# Microcontroller.net
KiCad netlist of a schematic drawn in Altium Designer
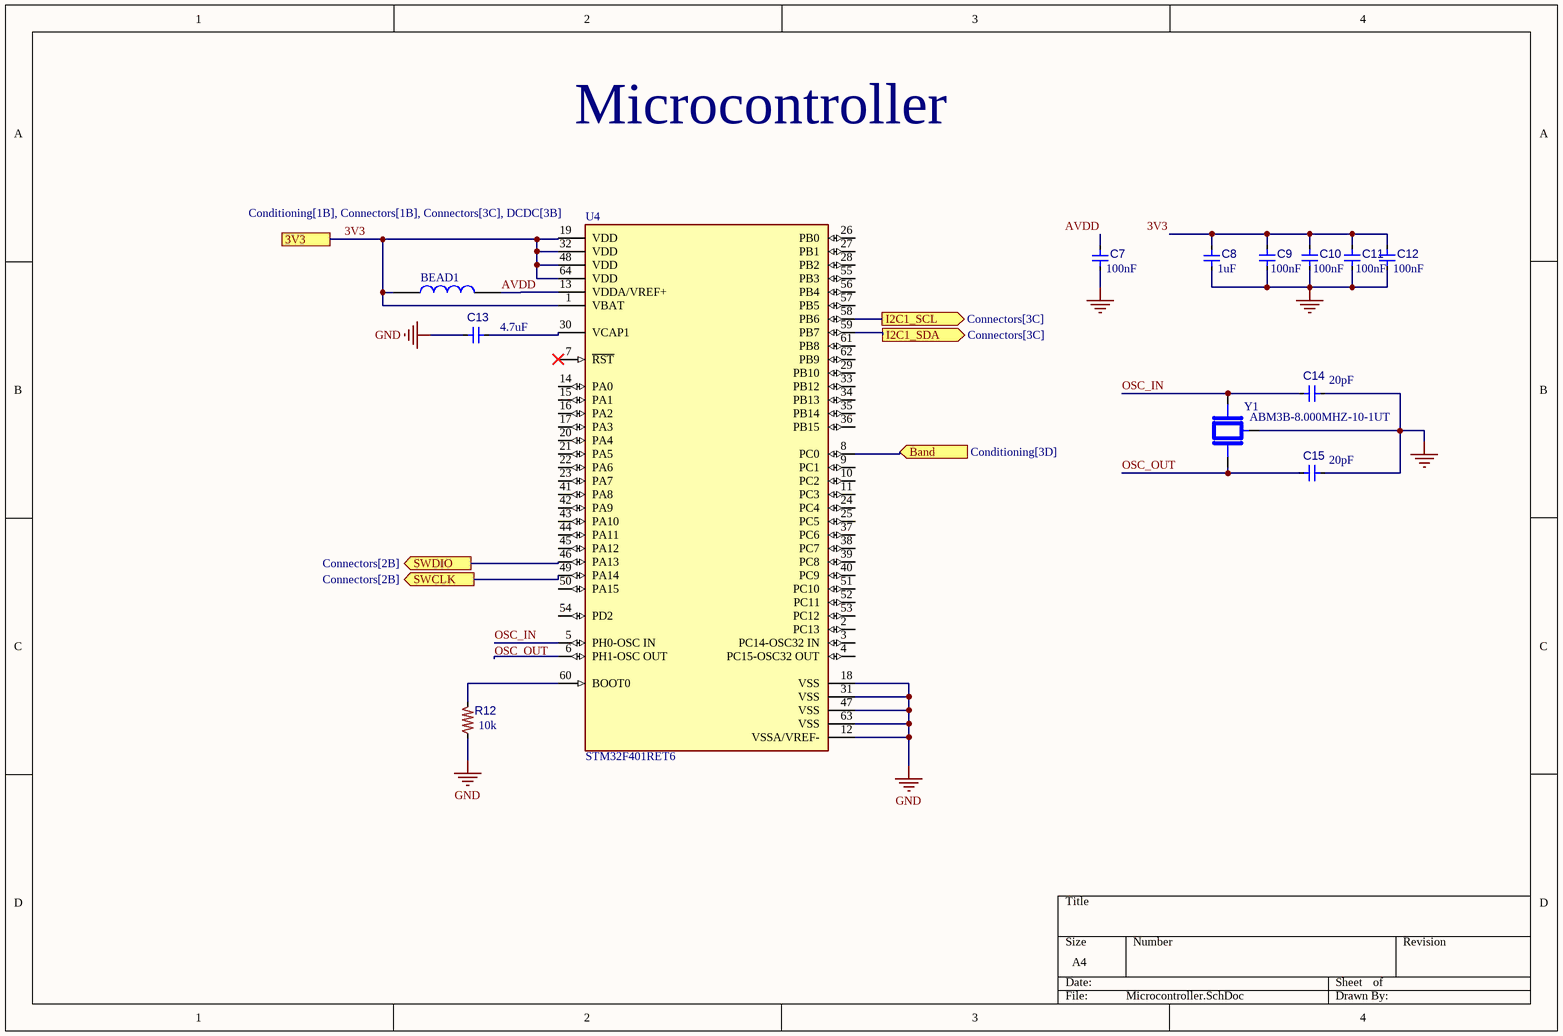
[diagram p0: Microcontroller.SchDoc]

(export (version "E")
  (design (tool "Eeschema 10.0.6"))
  (components
    (comp (ref "BEAD1")
      (value "C710390")
      (footprint "BEADC1608X95N")
      (description "MURATA Ferrite Beads 120 OHM - BLM18SG121TZ1D")
      (fields
        (field (name "MOUSER PART NUMBER") "791-WLBD1608K1U601TB")
        (field (name "MANUFACTURER_PART_NUMBER") "WLBD1608K1U601TB")
      )
      (libsource (lib "Muner") (part "WLBD1608K1U601TB"))
    )
    (comp (ref "C7")
      (value "C105907")
      (footprint "New footprint 1")
      (description "100V 100nF X7R ±10% 0603  Multilayer Ceramic Capacitors MLCC - SMD/SMT ROHS")
      (libsource (lib "Muner") (part "CAP-NP-2"))
    )
    (comp (ref "C8")
      (value "C309479")
      (footprint "New footprint 1")
      (description "6.3V 1uF X7R ±10% 0603  Multilayer Ceramic Capacitors MLCC - SMD/SMT ROHS")
      (libsource (lib "Muner") (part "CAP-NP-2"))
    )
    (comp (ref "C9")
      (value "C105907")
      (footprint "New footprint 1")
      (description "100V 100nF X7R ±10% 0603  Multilayer Ceramic Capacitors MLCC - SMD/SMT ROHS")
      (libsource (lib "Muner") (part "CAP-NP-2"))
    )
    (comp (ref "C10")
      (value "C105907")
      (footprint "New footprint 1")
      (description "100V 100nF X7R ±10% 0603  Multilayer Ceramic Capacitors MLCC - SMD/SMT ROHS")
      (libsource (lib "Muner") (part "CAP-NP-2"))
    )
    (comp (ref "C11")
      (value "C105907")
      (footprint "New footprint 1")
      (description "100V 100nF X7R ±10% 0603  Multilayer Ceramic Capacitors MLCC - SMD/SMT ROHS")
      (libsource (lib "Muner") (part "CAP-NP-2"))
    )
    (comp (ref "C12")
      (value "C105907")
      (footprint "New footprint 1")
      (description "100V 100nF X7R ±10% 0603  Multilayer Ceramic Capacitors MLCC - SMD/SMT ROHS")
      (libsource (lib "Muner") (part "CAP-NP-2"))
    )
    (comp (ref "C13")
      (value "C77045")
      (footprint "New footprint 1")
      (description "116V 4.7uF X5R ±10% 0603 Multilayer Ceramic Capacitors MLCC - SMD/SMT ROHS")
      (libsource (lib "Muner") (part "CAP-NP-2"))
    )
    (comp (ref "C14")
      (value "C63680")
      (footprint "New footprint 1")
      (description "200V 20pF C0G ±5% 0603 Multilayer Ceramic Capacitors MLCC - SMD/SMT ROHS")
      (libsource (lib "Muner") (part "CAP-NP-2"))
    )
    (comp (ref "C15")
      (value "C63680")
      (footprint "New footprint 1")
      (description "200V 20pF C0G ±5% 0603 Multilayer Ceramic Capacitors MLCC - SMD/SMT ROHS")
      (libsource (lib "Muner") (part "CAP-NP-2"))
    )
    (comp (ref "R12")
      (value "C103210")
      (footprint "0603 resistor-Footprint-1")
      (description "100mW Thick Film Resistors ±100ppm/℃ ±5% 10kΩ 0603 Chip Resistor - Surface Mount ROHS")
      (libsource (lib "Muner") (part "RES-2"))
    )
    (comp (ref "U4")
      (value "STM32F401RET6")
      (footprint "FP-LQFP64-5W-MFG")
      (description "512KB 1.7V~3.6V ARM Cortex-M4 84MHz 50 LQFP-64(10x10)  Microcontroller Units (MCUs/MPUs/SOCs) ROHS")
      (fields
        (field (name "OCTOPART") "https://octopart.com/stm32f401ret6-stmicroelectronics-34185993")
        (field (name "MANUFACTURER") "STMicroelectronics")
      )
      (libsource (lib "Altium Content Vault") (part "7f49e7cdc56bbeda8d86db7d775c506"))
    )
    (comp (ref "Y1")
      (value "ABM3B-8.000MHZ-10-1UT")
      (footprint "XTAL_ABM3B-8.000MHZ-10-1UT")
      (description "Crystal 8MHz Â±10ppm (Tol) Â±10ppm (Stability) 10pF FUND 200Ohm 4-Pin CSMD T/R")
      (fields (field (name "MF") "Abracon Corporation"))
      (libsource (lib "Muner") (part "CMP-003-00030-3"))
    )
  )
  (nets
    (net (code "1") (name "/3V3") (class "Default")
      (node (ref "BEAD1") (pin "1") (pinfunction "1_1") (pintype "passive"))
      (node (ref "C10") (pin "2") (pinfunction "2_2") (pintype "passive"))
      (node (ref "C11") (pin "2") (pinfunction "2_2") (pintype "passive"))
      (node (ref "C12") (pin "2") (pinfunction "2_2") (pintype "passive"))
      (node (ref "C8") (pin "2") (pinfunction "2_2") (pintype "passive"))
      (node (ref "C9") (pin "2") (pinfunction "2_2") (pintype "passive"))
      (node (ref "U4") (pin "1") (pinfunction "VBAT_1") (pintype "power_in"))
      (node (ref "U4") (pin "19") (pinfunction "VDD_19") (pintype "power_in"))
      (node (ref "U4") (pin "32") (pinfunction "VDD_32") (pintype "power_in"))
      (node (ref "U4") (pin "48") (pinfunction "VDD_48") (pintype "power_in"))
      (node (ref "U4") (pin "64") (pinfunction "VDD_64") (pintype "power_in"))
    )
    (net (code "2") (name "/AVDD") (class "Default")
      (node (ref "BEAD1") (pin "2") (pinfunction "2_2") (pintype "passive"))
      (node (ref "C7") (pin "2") (pinfunction "2_2") (pintype "passive"))
      (node (ref "U4") (pin "13") (pinfunction "VDDA/VREF+_13") (pintype "power_in"))
    )
    (net (code "3") (name "/Band") (class "Default")
      (node (ref "U4") (pin "8") (pinfunction "PC0_8") (pintype "bidirectional"))
    )
    (net (code "4") (name "/I2C1_SCL") (class "Default")
      (node (ref "U4") (pin "58") (pinfunction "PB6_58") (pintype "bidirectional"))
    )
    (net (code "5") (name "/I2C1_SDA") (class "Default")
      (node (ref "U4") (pin "59") (pinfunction "PB7_59") (pintype "bidirectional"))
    )
    (net (code "6") (name "/OSC_IN") (class "Default")
      (node (ref "C14") (pin "1") (pinfunction "1_1") (pintype "passive"))
      (node (ref "U4") (pin "5") (pinfunction "PH0-OSC_IN_5") (pintype "bidirectional"))
      (node (ref "Y1") (pin "3") (pinfunction "2_3") (pintype "passive"))
    )
    (net (code "7") (name "/OSC_OUT") (class "Default")
      (node (ref "C15") (pin "1") (pinfunction "1_1") (pintype "passive"))
      (node (ref "U4") (pin "6") (pinfunction "PH1-OSC_OUT_6") (pintype "bidirectional"))
      (node (ref "Y1") (pin "1") (pinfunction "1_1") (pintype "passive"))
    )
    (net (code "8") (name "/SWCLK") (class "Default")
      (node (ref "U4") (pin "49") (pinfunction "PA14_49") (pintype "bidirectional"))
    )
    (net (code "9") (name "/SWDIO") (class "Default")
      (node (ref "U4") (pin "46") (pinfunction "PA13_46") (pintype "bidirectional"))
    )
    (net (code "10") (name "GND") (class "Default")
      (node (ref "C10") (pin "1") (pinfunction "1_1") (pintype "passive"))
      (node (ref "C13") (pin "1") (pinfunction "1_1") (pintype "passive"))
      (node (ref "C14") (pin "2") (pinfunction "2_2") (pintype "passive"))
      (node (ref "C15") (pin "2") (pinfunction "2_2") (pintype "passive"))
      (node (ref "C7") (pin "1") (pinfunction "1_1") (pintype "passive"))
      (node (ref "C8") (pin "1") (pinfunction "1_1") (pintype "passive"))
      (node (ref "C9") (pin "1") (pinfunction "1_1") (pintype "passive"))
      (node (ref "R12") (pin "2") (pinfunction "2_2") (pintype "passive"))
      (node (ref "U4") (pin "12") (pinfunction "VSSA/VREF-_12") (pintype "power_in"))
      (node (ref "U4") (pin "18") (pinfunction "VSS_18") (pintype "power_in"))
      (node (ref "U4") (pin "31") (pinfunction "VSS_31") (pintype "power_in"))
      (node (ref "U4") (pin "47") (pinfunction "VSS_47") (pintype "power_in"))
      (node (ref "U4") (pin "63") (pinfunction "VSS_63") (pintype "power_in"))
      (node (ref "Y1") (pin "4") (pinfunction "4_4") (pintype "passive"))
    )
    (net (code "11") (name "Net-(C11-Pad1)") (class "Default")
      (node (ref "C11") (pin "1") (pinfunction "1_1") (pintype "passive"))
      (node (ref "C12") (pin "1") (pinfunction "1_1") (pintype "passive"))
    )
    (net (code "12") (name "Net-(U4-BOOT0)") (class "Default")
      (node (ref "R12") (pin "1") (pinfunction "1_1") (pintype "passive"))
      (node (ref "U4") (pin "60") (pinfunction "BOOT0_60") (pintype "input"))
    )
    (net (code "13") (name "Net-(U4-VCAP1)") (class "Default")
      (node (ref "C13") (pin "2") (pinfunction "2_2") (pintype "passive"))
      (node (ref "U4") (pin "30") (pinfunction "VCAP1_30") (pintype "power_in"))
    )
    (net (code "14") (name "unconnected-(U4-PA0-Pad14)") (class "Default")
      (node (ref "U4") (pin "14") (pinfunction "PA0_14") (pintype "bidirectional"))
    )
    (net (code "15") (name "unconnected-(U4-PA1-Pad15)") (class "Default")
      (node (ref "U4") (pin "15") (pinfunction "PA1_15") (pintype "bidirectional"))
    )
    (net (code "16") (name "unconnected-(U4-PA2-Pad16)") (class "Default")
      (node (ref "U4") (pin "16") (pinfunction "PA2_16") (pintype "bidirectional"))
    )
    (net (code "17") (name "unconnected-(U4-PA3-Pad17)") (class "Default")
      (node (ref "U4") (pin "17") (pinfunction "PA3_17") (pintype "bidirectional"))
    )
    (net (code "18") (name "unconnected-(U4-PA4-Pad20)") (class "Default")
      (node (ref "U4") (pin "20") (pinfunction "PA4_20") (pintype "bidirectional"))
    )
    (net (code "19") (name "unconnected-(U4-PA5-Pad21)") (class "Default")
      (node (ref "U4") (pin "21") (pinfunction "PA5_21") (pintype "bidirectional"))
    )
    (net (code "20") (name "unconnected-(U4-PA6-Pad22)") (class "Default")
      (node (ref "U4") (pin "22") (pinfunction "PA6_22") (pintype "bidirectional"))
    )
    (net (code "21") (name "unconnected-(U4-PA7-Pad23)") (class "Default")
      (node (ref "U4") (pin "23") (pinfunction "PA7_23") (pintype "bidirectional"))
    )
    (net (code "22") (name "unconnected-(U4-PA8-Pad41)") (class "Default")
      (node (ref "U4") (pin "41") (pinfunction "PA8_41") (pintype "bidirectional"))
    )
    (net (code "23") (name "unconnected-(U4-PA9-Pad42)") (class "Default")
      (node (ref "U4") (pin "42") (pinfunction "PA9_42") (pintype "bidirectional"))
    )
    (net (code "24") (name "unconnected-(U4-PA10-Pad43)") (class "Default")
      (node (ref "U4") (pin "43") (pinfunction "PA10_43") (pintype "bidirectional"))
    )
    (net (code "25") (name "unconnected-(U4-PA11-Pad44)") (class "Default")
      (node (ref "U4") (pin "44") (pinfunction "PA11_44") (pintype "bidirectional"))
    )
    (net (code "26") (name "unconnected-(U4-PA12-Pad45)") (class "Default")
      (node (ref "U4") (pin "45") (pinfunction "PA12_45") (pintype "bidirectional"))
    )
    (net (code "27") (name "unconnected-(U4-PA15-Pad50)") (class "Default")
      (node (ref "U4") (pin "50") (pinfunction "PA15_50") (pintype "bidirectional"))
    )
    (net (code "28") (name "unconnected-(U4-PB0-Pad26)") (class "Default")
      (node (ref "U4") (pin "26") (pinfunction "PB0_26") (pintype "bidirectional"))
    )
    (net (code "29") (name "unconnected-(U4-PB1-Pad27)") (class "Default")
      (node (ref "U4") (pin "27") (pinfunction "PB1_27") (pintype "bidirectional"))
    )
    (net (code "30") (name "unconnected-(U4-PB2-Pad28)") (class "Default")
      (node (ref "U4") (pin "28") (pinfunction "PB2_28") (pintype "bidirectional"))
    )
    (net (code "31") (name "unconnected-(U4-PB3-Pad55)") (class "Default")
      (node (ref "U4") (pin "55") (pinfunction "PB3_55") (pintype "bidirectional"))
    )
    (net (code "32") (name "unconnected-(U4-PB4-Pad56)") (class "Default")
      (node (ref "U4") (pin "56") (pinfunction "PB4_56") (pintype "bidirectional"))
    )
    (net (code "33") (name "unconnected-(U4-PB5-Pad57)") (class "Default")
      (node (ref "U4") (pin "57") (pinfunction "PB5_57") (pintype "bidirectional"))
    )
    (net (code "34") (name "unconnected-(U4-PB8-Pad61)") (class "Default")
      (node (ref "U4") (pin "61") (pinfunction "PB8_61") (pintype "bidirectional"))
    )
    (net (code "35") (name "unconnected-(U4-PB9-Pad62)") (class "Default")
      (node (ref "U4") (pin "62") (pinfunction "PB9_62") (pintype "bidirectional"))
    )
    (net (code "36") (name "unconnected-(U4-PB10-Pad29)") (class "Default")
      (node (ref "U4") (pin "29") (pinfunction "PB10_29") (pintype "bidirectional"))
    )
    (net (code "37") (name "unconnected-(U4-PB12-Pad33)") (class "Default")
      (node (ref "U4") (pin "33") (pinfunction "PB12_33") (pintype "bidirectional"))
    )
    (net (code "38") (name "unconnected-(U4-PB13-Pad34)") (class "Default")
      (node (ref "U4") (pin "34") (pinfunction "PB13_34") (pintype "bidirectional"))
    )
    (net (code "39") (name "unconnected-(U4-PB14-Pad35)") (class "Default")
      (node (ref "U4") (pin "35") (pinfunction "PB14_35") (pintype "bidirectional"))
    )
    (net (code "40") (name "unconnected-(U4-PB15-Pad36)") (class "Default")
      (node (ref "U4") (pin "36") (pinfunction "PB15_36") (pintype "bidirectional"))
    )
    (net (code "41") (name "unconnected-(U4-PC1-Pad9)") (class "Default")
      (node (ref "U4") (pin "9") (pinfunction "PC1_9") (pintype "bidirectional"))
    )
    (net (code "42") (name "unconnected-(U4-PC2-Pad10)") (class "Default")
      (node (ref "U4") (pin "10") (pinfunction "PC2_10") (pintype "bidirectional"))
    )
    (net (code "43") (name "unconnected-(U4-PC3-Pad11)") (class "Default")
      (node (ref "U4") (pin "11") (pinfunction "PC3_11") (pintype "bidirectional"))
    )
    (net (code "44") (name "unconnected-(U4-PC4-Pad24)") (class "Default")
      (node (ref "U4") (pin "24") (pinfunction "PC4_24") (pintype "bidirectional"))
    )
    (net (code "45") (name "unconnected-(U4-PC5-Pad25)") (class "Default")
      (node (ref "U4") (pin "25") (pinfunction "PC5_25") (pintype "bidirectional"))
    )
    (net (code "46") (name "unconnected-(U4-PC6-Pad37)") (class "Default")
      (node (ref "U4") (pin "37") (pinfunction "PC6_37") (pintype "bidirectional"))
    )
    (net (code "47") (name "unconnected-(U4-PC7-Pad38)") (class "Default")
      (node (ref "U4") (pin "38") (pinfunction "PC7_38") (pintype "bidirectional"))
    )
    (net (code "48") (name "unconnected-(U4-PC8-Pad39)") (class "Default")
      (node (ref "U4") (pin "39") (pinfunction "PC8_39") (pintype "bidirectional"))
    )
    (net (code "49") (name "unconnected-(U4-PC9-Pad40)") (class "Default")
      (node (ref "U4") (pin "40") (pinfunction "PC9_40") (pintype "bidirectional"))
    )
    (net (code "50") (name "unconnected-(U4-PC10-Pad51)") (class "Default")
      (node (ref "U4") (pin "51") (pinfunction "PC10_51") (pintype "bidirectional"))
    )
    (net (code "51") (name "unconnected-(U4-PC11-Pad52)") (class "Default")
      (node (ref "U4") (pin "52") (pinfunction "PC11_52") (pintype "bidirectional"))
    )
    (net (code "52") (name "unconnected-(U4-PC12-Pad53)") (class "Default")
      (node (ref "U4") (pin "53") (pinfunction "PC12_53") (pintype "bidirectional"))
    )
    (net (code "53") (name "unconnected-(U4-PC13-Pad2)") (class "Default")
      (node (ref "U4") (pin "2") (pinfunction "PC13_2") (pintype "bidirectional"))
    )
    (net (code "54") (name "unconnected-(U4-PC14-OSC32_IN-Pad3)") (class "Default")
      (node (ref "U4") (pin "3") (pinfunction "PC14-OSC32_IN_3") (pintype "bidirectional"))
    )
    (net (code "55") (name "unconnected-(U4-PC15-OSC32_OUT-Pad4)") (class "Default")
      (node (ref "U4") (pin "4") (pinfunction "PC15-OSC32_OUT_4") (pintype "bidirectional"))
    )
    (net (code "56") (name "unconnected-(U4-PD2-Pad54)") (class "Default")
      (node (ref "U4") (pin "54") (pinfunction "PD2_54") (pintype "bidirectional"))
    )
    (net (code "57") (name "unconnected-(U4-~{RST}-Pad7)") (class "Default")
      (node (ref "U4") (pin "7") (pinfunction "~{RST}_7") (pintype "input+no_connect"))
    )
  )
)
